# MCU_Module.net
KiCad netlist of a schematic drawn in Altium Designer
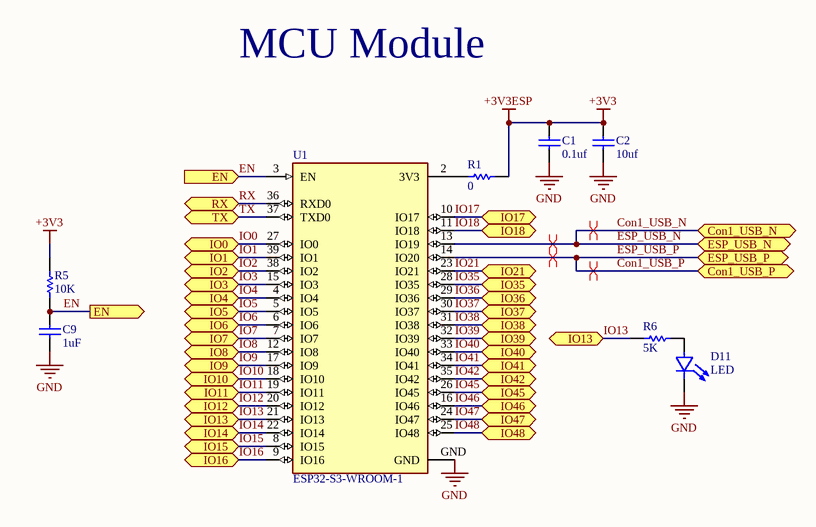
[diagram p0: MCU Module.SchDoc]

(export (version "E")
  (design (tool "Eeschema 10.0.6"))
  (components
    (comp (ref "C1") (value "0.1uf") (footprint "C0402") (libsource (lib "Schlib1") (part "Cap")))
    (comp (ref "C2") (value "10uf") (footprint "C0402") (libsource (lib "Schlib1") (part "Cap")))
    (comp (ref "C9") (value "1uF") (footprint "C0402") (libsource (lib "Schlib1") (part "Cap")))
    (comp (ref "D11") (value "LED") (footprint "LED0402") (libsource (lib "Schlib1") (part "LED")))
    (comp (ref "R1") (value "0") (footprint "R0402") (libsource (lib "Schlib1") (part "Res")))
    (comp (ref "R5") (value "10K") (footprint "R0402") (libsource (lib "Schlib1") (part "Res")))
    (comp (ref "R6") (value "5K") (footprint "R0402") (libsource (lib "Schlib1") (part "Res")))
    (comp (ref "U1")
      (value "ESP32-S3-WROOM-1")
      (footprint "ESP32")
      (description "Bluetooth, WiFi 802.11b/g/n, Bluetooth v5.0 Transceiver Module 2.4GHz PCB Trace Surface Mount")
      (libsource (lib "Schlib1") (part "ESP32-S3-WROOM-1"))
    )
  )
  (nets
    (net (code "1") (name "+3V3") (class "Default")
      (node (ref "C1") (pin "01") (pinfunction "+_01") (pintype "passive"))
      (node (ref "C2") (pin "01") (pinfunction "+_01") (pintype "passive"))
      (node (ref "R1") (pin "01") (pinfunction "01_01") (pintype "passive"))
      (node (ref "R5") (pin "02") (pinfunction "02_02") (pintype "passive"))
    )
    (net (code "2") (name "/Con1_USB_N") (class "Default")
      (node (ref "U1") (pin "13") (pinfunction "IO19_13") (pintype "bidirectional"))
    )
    (net (code "3") (name "/Con1_USB_P") (class "Default")
      (node (ref "U1") (pin "14") (pinfunction "IO20_14") (pintype "bidirectional"))
    )
    (net (code "4") (name "/EN") (class "Default")
      (node (ref "C9") (pin "02") (pinfunction "-_02") (pintype "passive"))
      (node (ref "R5") (pin "01") (pinfunction "01_01") (pintype "passive"))
      (node (ref "U1") (pin "3") (pinfunction "EN_3") (pintype "input"))
    )
    (net (code "5") (name "/IO0") (class "Default")
      (node (ref "U1") (pin "27") (pinfunction "IO0_27") (pintype "bidirectional"))
    )
    (net (code "6") (name "/IO1") (class "Default")
      (node (ref "U1") (pin "39") (pinfunction "IO1_39") (pintype "bidirectional"))
    )
    (net (code "7") (name "/IO2") (class "Default")
      (node (ref "U1") (pin "38") (pinfunction "IO2_38") (pintype "bidirectional"))
    )
    (net (code "8") (name "/IO3") (class "Default")
      (node (ref "U1") (pin "15") (pinfunction "IO3_15") (pintype "bidirectional"))
    )
    (net (code "9") (name "/IO4") (class "Default")
      (node (ref "U1") (pin "4") (pinfunction "IO4_4") (pintype "bidirectional"))
    )
    (net (code "10") (name "/IO5") (class "Default")
      (node (ref "U1") (pin "5") (pinfunction "IO5_5") (pintype "bidirectional"))
    )
    (net (code "11") (name "/IO6") (class "Default")
      (node (ref "U1") (pin "6") (pinfunction "IO6_6") (pintype "bidirectional"))
    )
    (net (code "12") (name "/IO7") (class "Default")
      (node (ref "U1") (pin "7") (pinfunction "IO7_7") (pintype "bidirectional"))
    )
    (net (code "13") (name "/IO8") (class "Default")
      (node (ref "U1") (pin "12") (pinfunction "IO8_12") (pintype "bidirectional"))
    )
    (net (code "14") (name "/IO9") (class "Default")
      (node (ref "U1") (pin "17") (pinfunction "IO9_17") (pintype "bidirectional"))
    )
    (net (code "15") (name "/IO10") (class "Default")
      (node (ref "U1") (pin "18") (pinfunction "IO10_18") (pintype "bidirectional"))
    )
    (net (code "16") (name "/IO11") (class "Default")
      (node (ref "U1") (pin "19") (pinfunction "IO11_19") (pintype "bidirectional"))
    )
    (net (code "17") (name "/IO12") (class "Default")
      (node (ref "U1") (pin "20") (pinfunction "IO12_20") (pintype "bidirectional"))
    )
    (net (code "18") (name "/IO13") (class "Default")
      (node (ref "R6") (pin "02") (pinfunction "02_02") (pintype "passive"))
      (node (ref "U1") (pin "21") (pinfunction "IO13_21") (pintype "bidirectional"))
    )
    (net (code "19") (name "/IO14") (class "Default")
      (node (ref "U1") (pin "22") (pinfunction "IO14_22") (pintype "bidirectional"))
    )
    (net (code "20") (name "/IO15") (class "Default")
      (node (ref "U1") (pin "8") (pinfunction "IO15_8") (pintype "bidirectional"))
    )
    (net (code "21") (name "/IO16") (class "Default")
      (node (ref "U1") (pin "9") (pinfunction "IO16_9") (pintype "bidirectional"))
    )
    (net (code "22") (name "/IO17") (class "Default")
      (node (ref "U1") (pin "10") (pinfunction "IO17_10") (pintype "bidirectional"))
    )
    (net (code "23") (name "/IO18") (class "Default")
      (node (ref "U1") (pin "11") (pinfunction "IO18_11") (pintype "bidirectional"))
    )
    (net (code "24") (name "/IO21") (class "Default")
      (node (ref "U1") (pin "23") (pinfunction "IO21_23") (pintype "bidirectional"))
    )
    (net (code "25") (name "/IO35") (class "Default")
      (node (ref "U1") (pin "28") (pinfunction "IO35_28") (pintype "bidirectional"))
    )
    (net (code "26") (name "/IO36") (class "Default")
      (node (ref "U1") (pin "29") (pinfunction "IO36_29") (pintype "bidirectional"))
    )
    (net (code "27") (name "/IO37") (class "Default")
      (node (ref "U1") (pin "30") (pinfunction "IO37_30") (pintype "bidirectional"))
    )
    (net (code "28") (name "/IO38") (class "Default")
      (node (ref "U1") (pin "31") (pinfunction "IO38_31") (pintype "bidirectional"))
    )
    (net (code "29") (name "/IO39") (class "Default")
      (node (ref "U1") (pin "32") (pinfunction "IO39_32") (pintype "bidirectional"))
    )
    (net (code "30") (name "/IO40") (class "Default")
      (node (ref "U1") (pin "33") (pinfunction "IO40_33") (pintype "bidirectional"))
    )
    (net (code "31") (name "/IO41") (class "Default")
      (node (ref "U1") (pin "34") (pinfunction "IO41_34") (pintype "bidirectional"))
    )
    (net (code "32") (name "/IO42") (class "Default")
      (node (ref "U1") (pin "35") (pinfunction "IO42_35") (pintype "bidirectional"))
    )
    (net (code "33") (name "/IO45") (class "Default")
      (node (ref "U1") (pin "26") (pinfunction "IO45_26") (pintype "bidirectional"))
    )
    (net (code "34") (name "/IO46") (class "Default")
      (node (ref "U1") (pin "16") (pinfunction "IO46_16") (pintype "bidirectional"))
    )
    (net (code "35") (name "/IO47") (class "Default")
      (node (ref "U1") (pin "24") (pinfunction "IO47_24") (pintype "bidirectional"))
    )
    (net (code "36") (name "/IO48") (class "Default")
      (node (ref "U1") (pin "25") (pinfunction "IO48_25") (pintype "bidirectional"))
    )
    (net (code "37") (name "/RX") (class "Default")
      (node (ref "U1") (pin "36") (pinfunction "RXD0_36") (pintype "bidirectional"))
    )
    (net (code "38") (name "/TX") (class "Default")
      (node (ref "U1") (pin "37") (pinfunction "TXD0_37") (pintype "bidirectional"))
    )
    (net (code "39") (name "GND") (class "Default")
      (node (ref "C1") (pin "02") (pinfunction "-_02") (pintype "passive"))
      (node (ref "C2") (pin "02") (pinfunction "-_02") (pintype "passive"))
      (node (ref "C9") (pin "01") (pinfunction "+_01") (pintype "passive"))
      (node (ref "D11") (pin "1") (pinfunction "C_1") (pintype "passive"))
      (node (ref "U1") (pin "GND") (pinfunction "GND_GND") (pintype "power_in"))
    )
    (net (code "40") (name "Net-(D11-A)") (class "Default")
      (node (ref "D11") (pin "2") (pinfunction "A_2") (pintype "passive"))
      (node (ref "R6") (pin "01") (pinfunction "01_01") (pintype "passive"))
    )
    (net (code "41") (name "Net-(U1-3V3)") (class "Default")
      (node (ref "R1") (pin "02") (pinfunction "02_02") (pintype "passive"))
      (node (ref "U1") (pin "2") (pinfunction "3V3_2") (pintype "power_in"))
    )
  )
)
